# Sheet1.net
KiCad netlist of a schematic drawn in Altium Designer
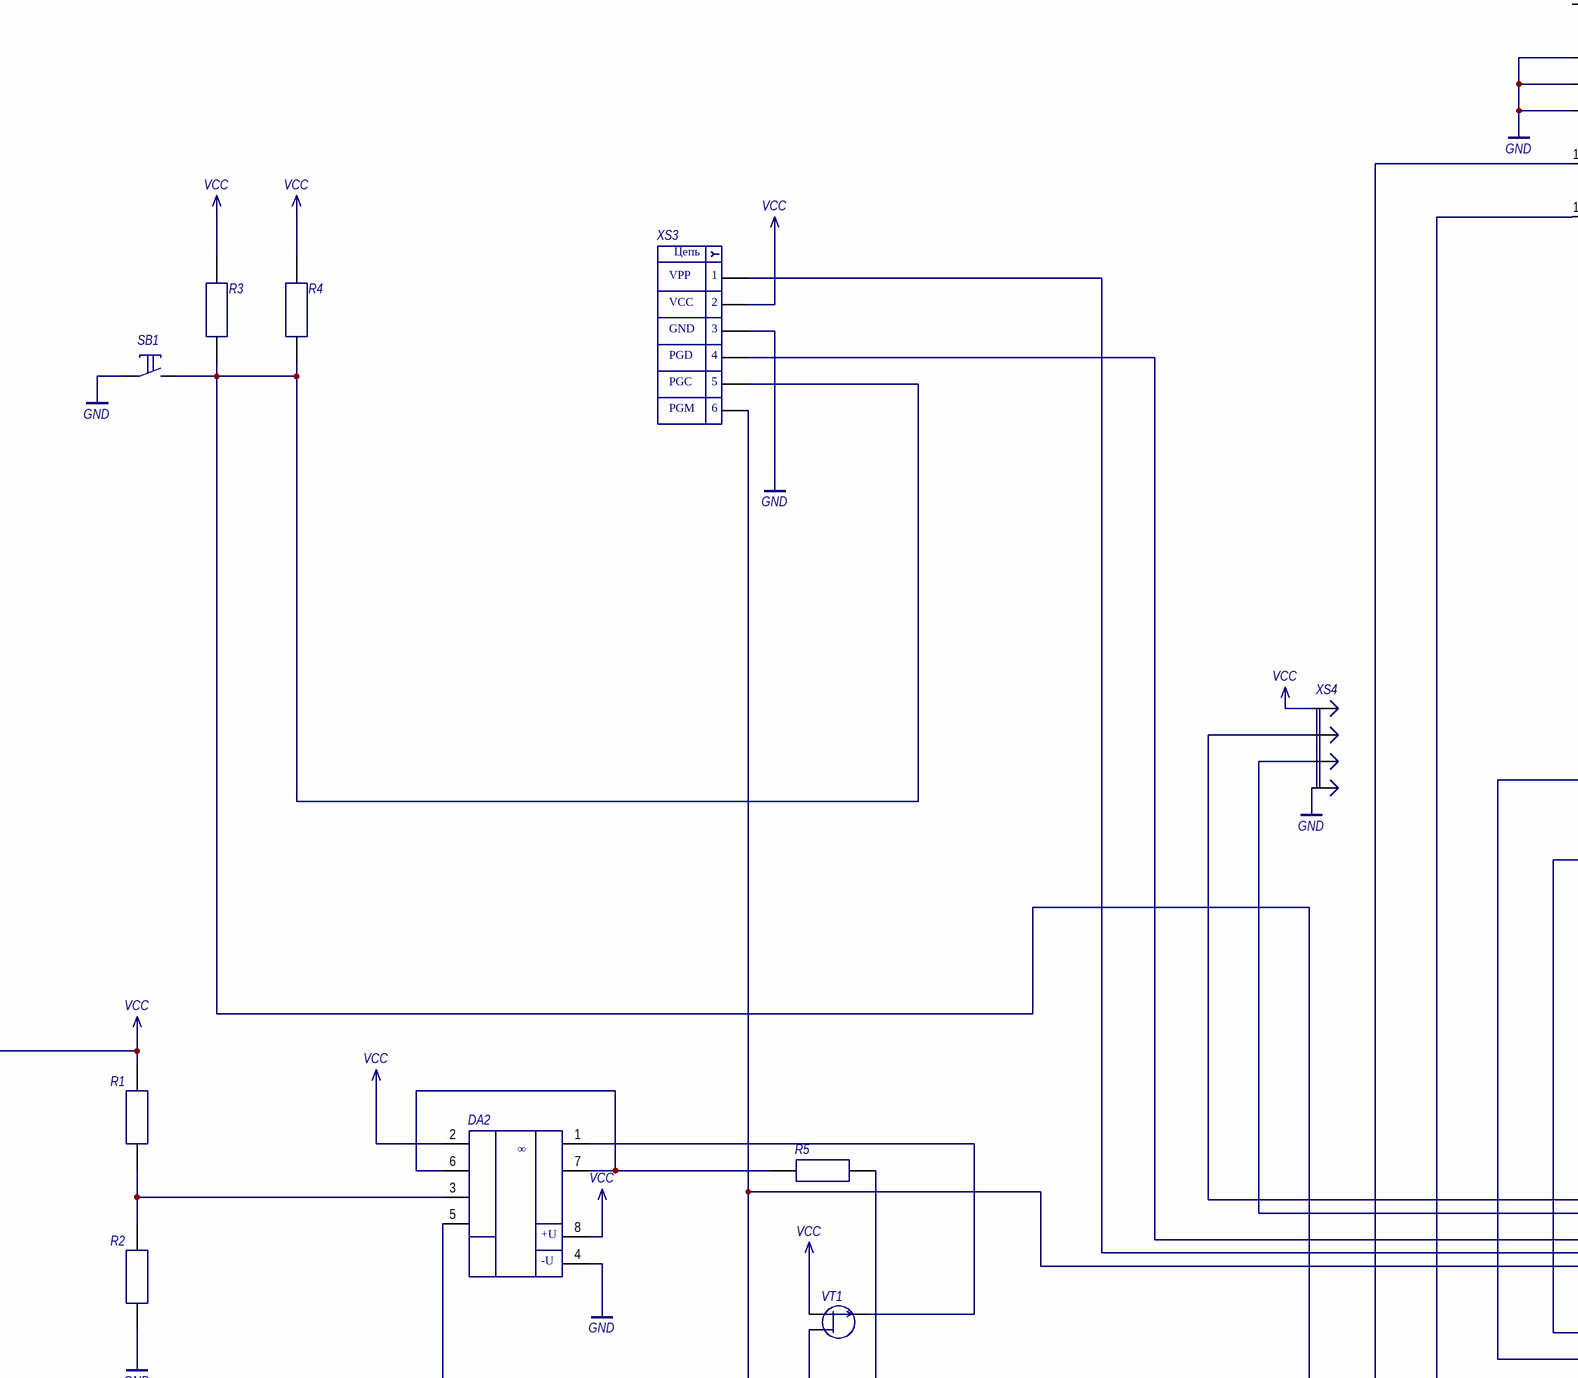
[diagram p0: Sheet1.SchDoc, top left]
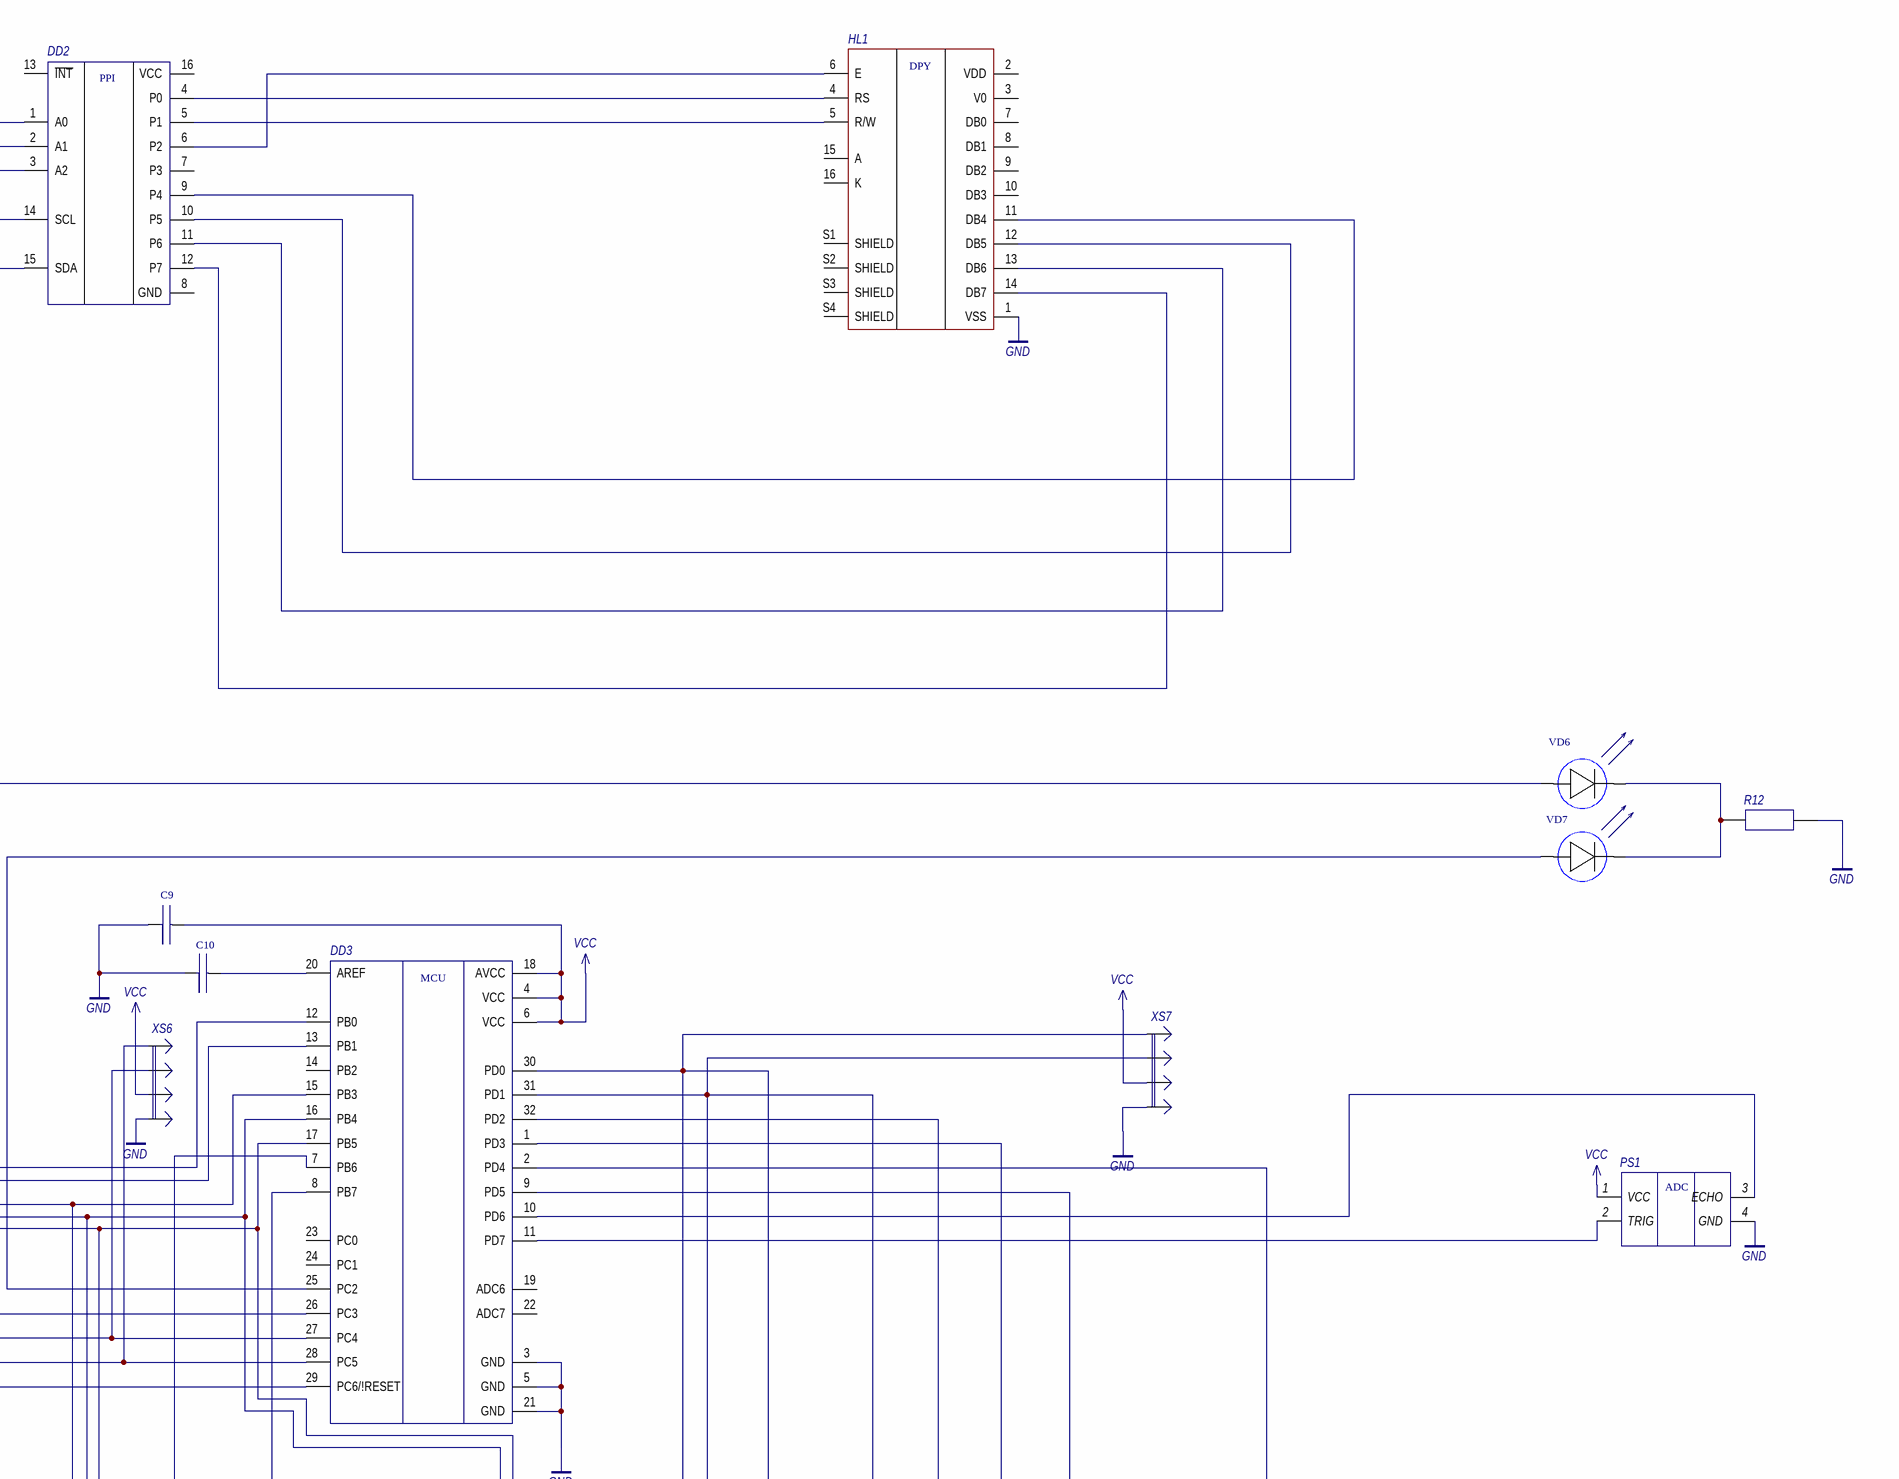
[diagram p1: Sheet1.SchDoc, top right]
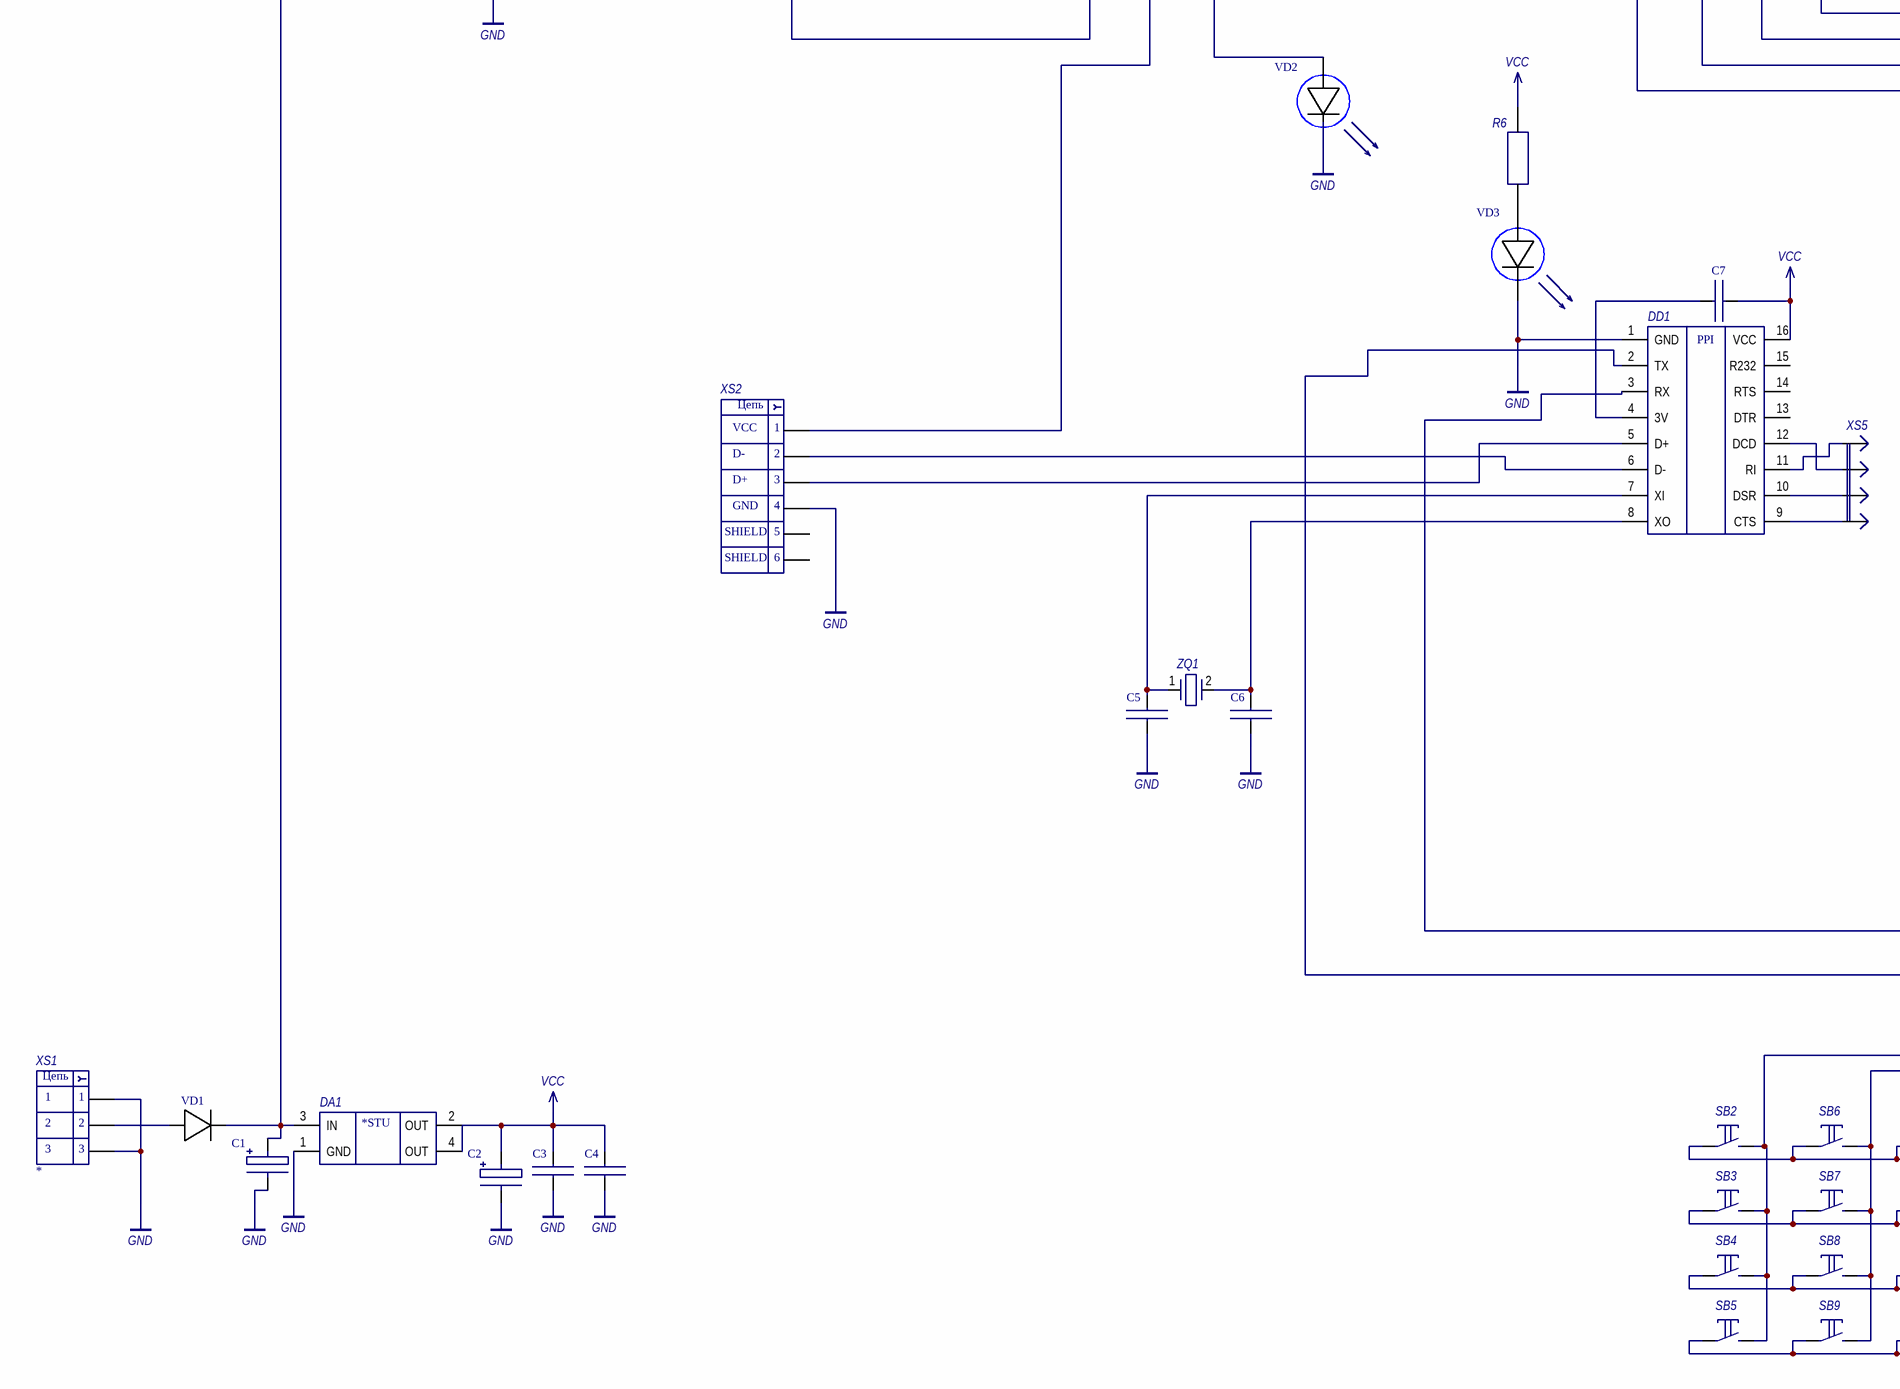
[diagram p2: Sheet1.SchDoc, bottom left]
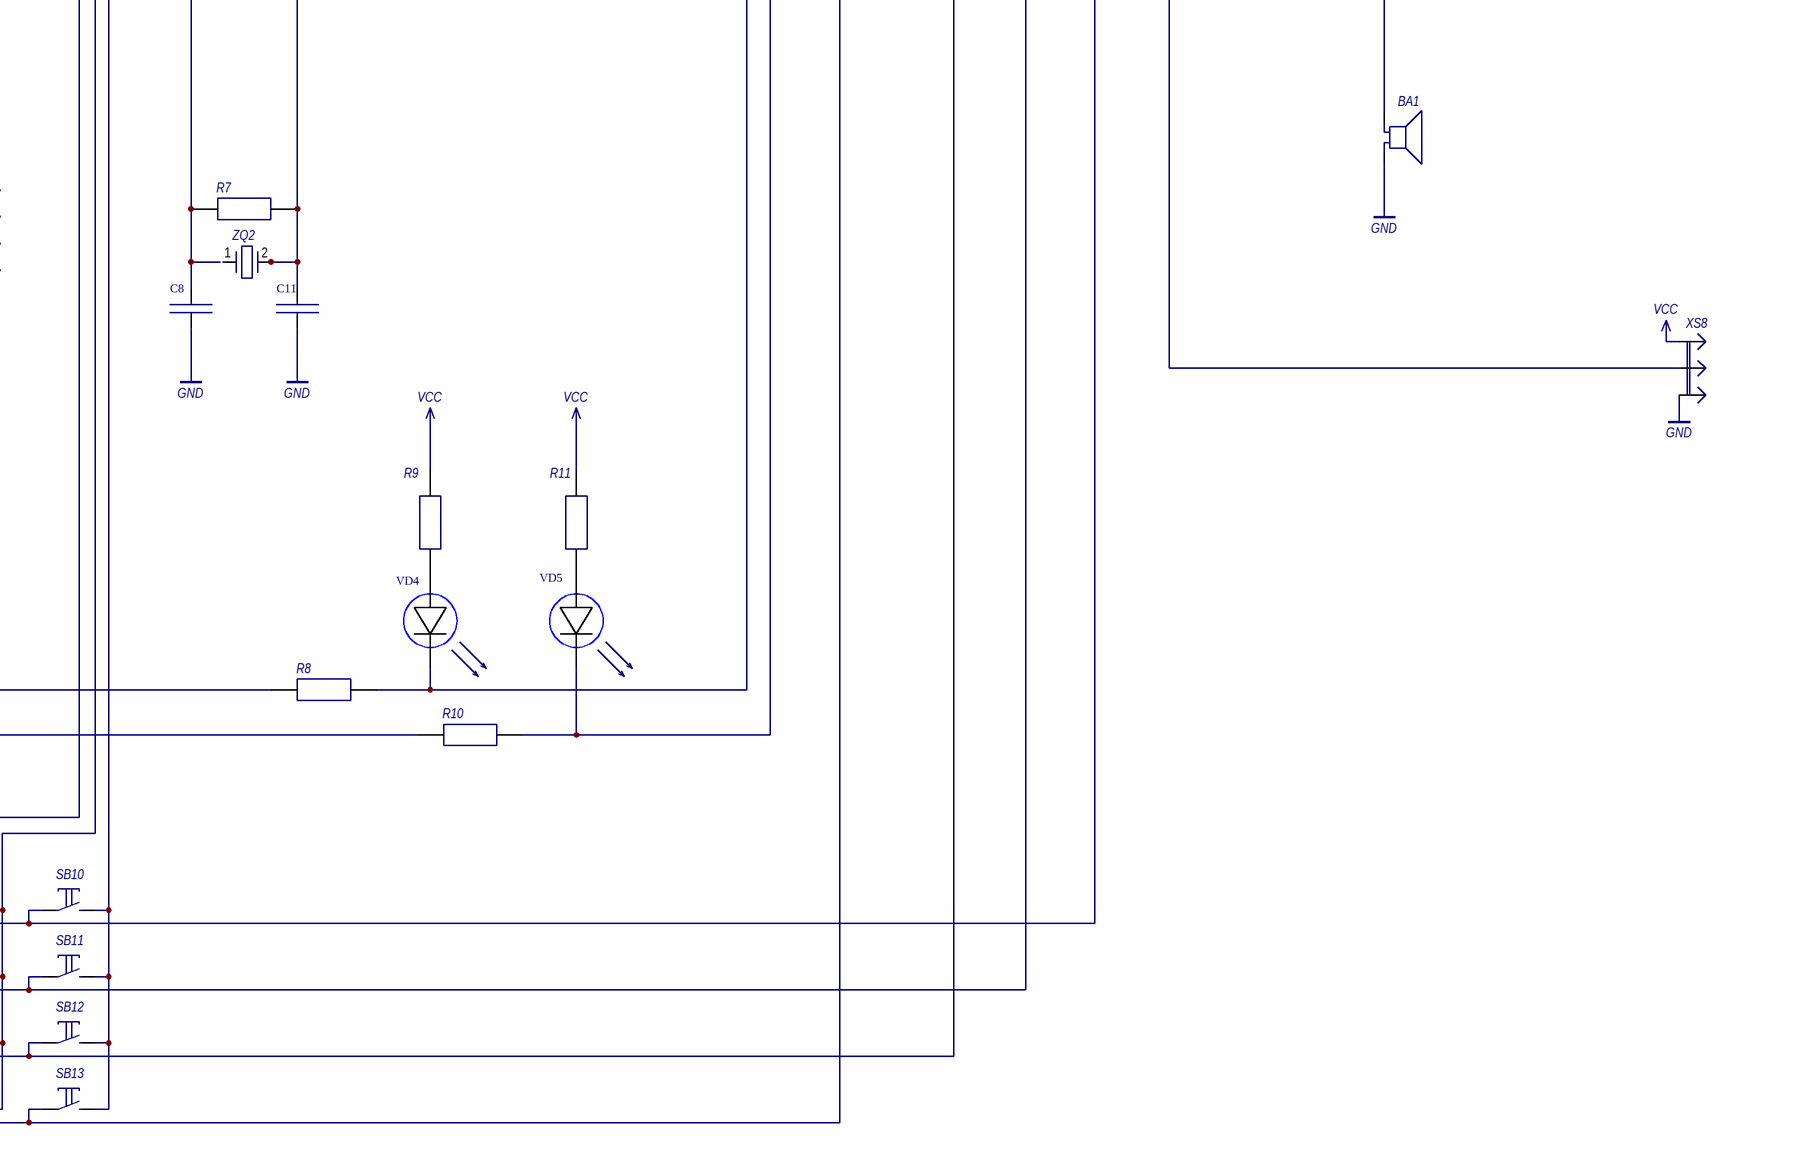
[diagram p3: Sheet1.SchDoc, bottom right]

(export (version "E")
  (design (tool "Eeschema 10.0.6"))
  (components
    (comp (ref "BA1")
      (value "*")
      (footprint "CUI_CVS-3108")
      (description "31.8 mm, Round Frame, 0.1 W, 8 Ohm, Neodymium Magnet, Mylar Cone, Speaker")
      (fields (field (name "MF") "CUI Devices") (field (name "MP") "CVS-3108"))
      (libsource (lib "CVS-3108") (part "CVS-3108"))
    )
    (comp (ref "C1")
      (value "UPM1C152MHD")
      (footprint "M7:SMA/DO-214AC_DTC")
      (description "1500ÂµF 16V Aluminum Electrolytic Capacitors Radial, Can 5000 Hrs @ 105Â°C")
      (fields (field (name "MF") "Nichicon"))
      (libsource (lib "UPM1C152MHD") (part "UPM1C152MHD"))
    )
    (comp (ref "C2")
      (value "UPM1C152MHD")
      (footprint "M7:SMA/DO-214AC_DTC")
      (description "1500ÂµF 16V Aluminum Electrolytic Capacitors Radial, Can 5000 Hrs @ 105Â°C")
      (fields (field (name "MF") "Nichicon"))
      (libsource (lib "UPM1C152MHD") (part "UPM1C152MHD"))
    )
    (comp (ref "C3")
      (value "1808Y5K00101JXT")
      (footprint "CAPC4520X200N:CAPC4520X200N")
      (libsource (lib "1808Y5K00101JXT") (part "1808Y5K00101JXT"))
    )
    (comp (ref "C4")
      (value "1808Y5K00101JXT")
      (footprint "CAPC4520X200N:CAPC4520X200N")
      (libsource (lib "1808Y5K00101JXT") (part "1808Y5K00101JXT"))
    )
    (comp (ref "C5")
      (value "1808Y5K00101JXT")
      (footprint "CAPC4520X200N:CAPC4520X200N")
      (libsource (lib "1808Y5K00101JXT") (part "1808Y5K00101JXT"))
    )
    (comp (ref "C6")
      (value "1808Y5K00101JXT")
      (footprint "CAPC4520X200N:CAPC4520X200N")
      (libsource (lib "1808Y5K00101JXT") (part "1808Y5K00101JXT"))
    )
    (comp (ref "C7")
      (value "1808Y5K00101JXT")
      (footprint "CAPC4520X200N:CAPC4520X200N")
      (libsource (lib "1808Y5K00101JXT") (part "1808Y5K00101JXT"))
    )
    (comp (ref "C8")
      (value "1808Y5K00101JXT")
      (footprint "CAPC4520X200N:CAPC4520X200N")
      (libsource (lib "1808Y5K00101JXT") (part "1808Y5K00101JXT"))
    )
    (comp (ref "C9")
      (value "1808Y5K00101JXT")
      (footprint "CAPC4520X200N:CAPC4520X200N")
      (libsource (lib "1808Y5K00101JXT") (part "1808Y5K00101JXT"))
    )
    (comp (ref "C10")
      (value "1808Y5K00101JXT")
      (footprint "CAPC4520X200N:CAPC4520X200N")
      (libsource (lib "1808Y5K00101JXT") (part "1808Y5K00101JXT"))
    )
    (comp (ref "C11")
      (value "1808Y5K00101JXT")
      (footprint "CAPC4520X200N:CAPC4520X200N")
      (libsource (lib "1808Y5K00101JXT") (part "1808Y5K00101JXT"))
    )
    (comp (ref "DA1")
      (value "*")
      (footprint "SOT230P700X180-4N")
      (description "Linear Voltage Regulator IC 1 Output 1A SOT-223")
      (fields (field (name "MP") "NCP1117ST50T3G") (field (name "MF") "ON Semiconductor"))
      (libsource (lib "NCP1117ST50T3G") (part "NCP1117ST50T3G"))
    )
    (comp (ref "DA2")
      (value "*")
      (footprint "SOIC127P599X175-8N")
      (description "Dual standard operational amplifier 8-SOIC 0 to 70")
      (fields (field (name "DIGI-KEY_PART_NUMBER") "296-1014-2-ND") (field (name "MP") "LM358D"))
      (libsource (lib "LM358D") (part "LM358D"))
    )
    (comp (ref "DD1")
      (value "*")
      (footprint "SOIC127P1030X265-16N")
      (description "Circuit Breaker Magnetic 3Pole 40A 240VAC")
      (fields (field (name "MF") "Eaton") (field (name "MP") "CH340"))
      (libsource (lib "CH340") (part "CH340"))
    )
    (comp (ref "DD2")
      (value "*")
      (footprint "DIP794W45P254L1969H508Q16")
      (description "Remote 8-Bit I/O Expander for I2C-Bus")
      (fields (field (name "MF") "Texas Instruments") (field (name "MP") "PCF8574N"))
      (libsource (lib "PCF8574N") (part "PCF8574N"))
    )
    (comp (ref "DD3")
      (value "*")
      (footprint "QFP80P900X900X120-32N")
      (description "AVR AVRÂ® ATmega Microcontroller IC 8-Bit 20MHz 32KB _16K x 16_ FLASH 32-TQFP _7x7_")
      (fields (field (name "MP") "ATMEGA328P-AU") (field (name "MF") "Microchip"))
      (libsource (lib "ATMEGA328P-AU") (part "ATMEGA328P-AU"))
    )
    (comp (ref "HL1")
      (value "*")
      (footprint "LCD_LCD-20X4B")
      (description "Display Development Tools 20X4 CHARACTER BLUE LCD W/BACKLIGHT")
      (fields (field (name "MF") "Gravitech") (field (name "MP") "LCD-20X4B"))
      (libsource (lib "LCD-20X4B") (part "LCD-20X4B"))
    )
    (comp (ref "PS1")
      (value "*")
      (footprint "XCVR_HC-SR04")
      (description "HC-SR04 Ultrasonic Sensor Platform Evaluation Expansion Board")
      (fields (field (name "MP") "HC-SR04") (field (name "MF") "SparkFun Electronics"))
      (libsource (lib "HC-SR04") (part "HC-SR04"))
    )
    (comp (ref "R1")
      (value "*")
      (footprint "CAPC4520X200N:CAPC4520X200N")
      (libsource (lib "R") (part "Component_1"))
    )
    (comp (ref "R2")
      (value "*")
      (footprint "CAPC4520X200N:CAPC4520X200N")
      (libsource (lib "R") (part "Component_1"))
    )
    (comp (ref "R3")
      (value "*")
      (footprint "CAPC4520X200N:CAPC4520X200N")
      (libsource (lib "R") (part "Component_1"))
    )
    (comp (ref "R4")
      (value "*")
      (footprint "CAPC4520X200N:CAPC4520X200N")
      (libsource (lib "R") (part "Component_1"))
    )
    (comp (ref "R5")
      (value "*")
      (footprint "CAPC4520X200N:CAPC4520X200N")
      (libsource (lib "R") (part "Component_1"))
    )
    (comp (ref "R6")
      (value "*")
      (footprint "CAPC4520X200N:CAPC4520X200N")
      (libsource (lib "R") (part "Component_1"))
    )
    (comp (ref "R7")
      (value "*")
      (footprint "CAPC4520X200N:CAPC4520X200N")
      (libsource (lib "R") (part "Component_1"))
    )
    (comp (ref "R8")
      (value "*")
      (footprint "CAPC4520X200N:CAPC4520X200N")
      (libsource (lib "R") (part "Component_1"))
    )
    (comp (ref "R9")
      (value "*")
      (footprint "CAPC4520X200N:CAPC4520X200N")
      (libsource (lib "R") (part "Component_1"))
    )
    (comp (ref "R10")
      (value "*")
      (footprint "CAPC4520X200N:CAPC4520X200N")
      (libsource (lib "R") (part "Component_1"))
    )
    (comp (ref "R11")
      (value "*")
      (footprint "CAPC4520X200N:CAPC4520X200N")
      (libsource (lib "R") (part "Component_1"))
    )
    (comp (ref "R12")
      (value "*")
      (footprint "CAPC4520X200N:CAPC4520X200N")
      (libsource (lib "R") (part "Component_1"))
    )
    (comp (ref "SB1")
      (value "4-1437565-9")
      (footprint "TE_4-1437565-9")
      (description "Switch Tactile OFF _ON_ SPST Round Button Gull Wing 0.05A 12VDC 1.57N SMD Loose Piece")
      (fields (field (name "MF") "TE Connectivity") (field (name "DIGI-KEY_PART_NUMBER") "450-1133-ND"))
      (libsource (lib "4-1437565-9") (part "4-1437565-9"))
    )
    (comp (ref "SB2")
      (value "4-1437565-9")
      (footprint "TE_4-1437565-9")
      (description "Switch Tactile OFF _ON_ SPST Round Button Gull Wing 0.05A 12VDC 1.57N SMD Loose Piece")
      (fields (field (name "MF") "TE Connectivity") (field (name "DIGI-KEY_PART_NUMBER") "450-1133-ND"))
      (libsource (lib "4-1437565-9") (part "4-1437565-9"))
    )
    (comp (ref "SB3")
      (value "4-1437565-9")
      (footprint "TE_4-1437565-9")
      (description "Switch Tactile OFF _ON_ SPST Round Button Gull Wing 0.05A 12VDC 1.57N SMD Loose Piece")
      (fields (field (name "MF") "TE Connectivity") (field (name "DIGI-KEY_PART_NUMBER") "450-1133-ND"))
      (libsource (lib "4-1437565-9") (part "4-1437565-9"))
    )
    (comp (ref "SB4")
      (value "4-1437565-9")
      (footprint "TE_4-1437565-9")
      (description "Switch Tactile OFF _ON_ SPST Round Button Gull Wing 0.05A 12VDC 1.57N SMD Loose Piece")
      (fields (field (name "MF") "TE Connectivity") (field (name "DIGI-KEY_PART_NUMBER") "450-1133-ND"))
      (libsource (lib "4-1437565-9") (part "4-1437565-9"))
    )
    (comp (ref "SB5")
      (value "4-1437565-9")
      (footprint "TE_4-1437565-9")
      (description "Switch Tactile OFF _ON_ SPST Round Button Gull Wing 0.05A 12VDC 1.57N SMD Loose Piece")
      (fields (field (name "MF") "TE Connectivity") (field (name "DIGI-KEY_PART_NUMBER") "450-1133-ND"))
      (libsource (lib "4-1437565-9") (part "4-1437565-9"))
    )
    (comp (ref "SB6")
      (value "4-1437565-9")
      (footprint "TE_4-1437565-9")
      (description "Switch Tactile OFF _ON_ SPST Round Button Gull Wing 0.05A 12VDC 1.57N SMD Loose Piece")
      (fields (field (name "MF") "TE Connectivity") (field (name "DIGI-KEY_PART_NUMBER") "450-1133-ND"))
      (libsource (lib "4-1437565-9") (part "4-1437565-9"))
    )
    (comp (ref "SB7")
      (value "4-1437565-9")
      (footprint "TE_4-1437565-9")
      (description "Switch Tactile OFF _ON_ SPST Round Button Gull Wing 0.05A 12VDC 1.57N SMD Loose Piece")
      (fields (field (name "MF") "TE Connectivity") (field (name "DIGI-KEY_PART_NUMBER") "450-1133-ND"))
      (libsource (lib "4-1437565-9") (part "4-1437565-9"))
    )
    (comp (ref "SB8")
      (value "4-1437565-9")
      (footprint "TE_4-1437565-9")
      (description "Switch Tactile OFF _ON_ SPST Round Button Gull Wing 0.05A 12VDC 1.57N SMD Loose Piece")
      (fields (field (name "MF") "TE Connectivity") (field (name "DIGI-KEY_PART_NUMBER") "450-1133-ND"))
      (libsource (lib "4-1437565-9") (part "4-1437565-9"))
    )
    (comp (ref "SB9")
      (value "4-1437565-9")
      (footprint "TE_4-1437565-9")
      (description "Switch Tactile OFF _ON_ SPST Round Button Gull Wing 0.05A 12VDC 1.57N SMD Loose Piece")
      (fields (field (name "MF") "TE Connectivity") (field (name "DIGI-KEY_PART_NUMBER") "450-1133-ND"))
      (libsource (lib "4-1437565-9") (part "4-1437565-9"))
    )
    (comp (ref "SB10")
      (value "4-1437565-9")
      (footprint "TE_4-1437565-9")
      (description "Switch Tactile OFF _ON_ SPST Round Button Gull Wing 0.05A 12VDC 1.57N SMD Loose Piece")
      (fields (field (name "MF") "TE Connectivity") (field (name "DIGI-KEY_PART_NUMBER") "450-1133-ND"))
      (libsource (lib "4-1437565-9") (part "4-1437565-9"))
    )
    (comp (ref "SB11")
      (value "4-1437565-9")
      (footprint "TE_4-1437565-9")
      (description "Switch Tactile OFF _ON_ SPST Round Button Gull Wing 0.05A 12VDC 1.57N SMD Loose Piece")
      (fields (field (name "MF") "TE Connectivity") (field (name "DIGI-KEY_PART_NUMBER") "450-1133-ND"))
      (libsource (lib "4-1437565-9") (part "4-1437565-9"))
    )
    (comp (ref "SB12")
      (value "4-1437565-9")
      (footprint "TE_4-1437565-9")
      (description "Switch Tactile OFF _ON_ SPST Round Button Gull Wing 0.05A 12VDC 1.57N SMD Loose Piece")
      (fields (field (name "MF") "TE Connectivity") (field (name "DIGI-KEY_PART_NUMBER") "450-1133-ND"))
      (libsource (lib "4-1437565-9") (part "4-1437565-9"))
    )
    (comp (ref "SB13")
      (value "4-1437565-9")
      (footprint "TE_4-1437565-9")
      (description "Switch Tactile OFF _ON_ SPST Round Button Gull Wing 0.05A 12VDC 1.57N SMD Loose Piece")
      (fields (field (name "MF") "TE Connectivity") (field (name "DIGI-KEY_PART_NUMBER") "450-1133-ND"))
      (libsource (lib "4-1437565-9") (part "4-1437565-9"))
    )
    (comp (ref "VD1")
      (value "1N4007")
      (footprint "SnapEDApcb:DIOAD1060W80L520D270")
      (description "Diode Standard 1000V 1A Through Hole DO-204AL _DO-41_")
      (fields (field (name "MF") "ON Semiconductor"))
      (libsource (lib "SnapEDAsch") (part "1N4007"))
    )
    (comp (ref "VD2")
      (value "CLA1A-WKW-CXAYB153")
      (footprint "SnapEDApcb:SOJ150P350X210-4N")
      (description "LED Lighting - White, Cool 5500K 3.6V 30mA 4-PLCC")
      (fields (field (name "MF") "Cree Inc.") (field (name "DIGI-KEY_PART_NUMBER") "CLA1A-WKW-CXAYB153CT-ND"))
      (libsource (lib "SnapEDAsch") (part "CLA1A-WKW-CXAYB153"))
    )
    (comp (ref "VD3")
      (value "CLA1A-WKW-CXAYB153")
      (footprint "SnapEDApcb:SOJ150P350X210-4N")
      (description "LED Lighting - White, Cool 5500K 3.6V 30mA 4-PLCC")
      (fields (field (name "MF") "Cree Inc.") (field (name "DIGI-KEY_PART_NUMBER") "CLA1A-WKW-CXAYB153CT-ND"))
      (libsource (lib "SnapEDAsch") (part "CLA1A-WKW-CXAYB153"))
    )
    (comp (ref "VD4")
      (value "CLA1A-WKW-CXAYB153")
      (footprint "SnapEDApcb:SOJ150P350X210-4N")
      (description "LED Lighting - White, Cool 5500K 3.6V 30mA 4-PLCC")
      (fields (field (name "MF") "Cree Inc.") (field (name "DIGI-KEY_PART_NUMBER") "CLA1A-WKW-CXAYB153CT-ND"))
      (libsource (lib "SnapEDAsch") (part "CLA1A-WKW-CXAYB153"))
    )
    (comp (ref "VD5")
      (value "CLA1A-WKW-CXAYB153")
      (footprint "SnapEDApcb:SOJ150P350X210-4N")
      (description "LED Lighting - White, Cool 5500K 3.6V 30mA 4-PLCC")
      (fields (field (name "MF") "Cree Inc.") (field (name "DIGI-KEY_PART_NUMBER") "CLA1A-WKW-CXAYB153CT-ND"))
      (libsource (lib "SnapEDAsch") (part "CLA1A-WKW-CXAYB153"))
    )
    (comp (ref "VD6")
      (value "CLA1A-WKW-CXAYB153")
      (footprint "SnapEDApcb:SOJ150P350X210-4N")
      (description "LED Lighting - White, Cool 5500K 3.6V 30mA 4-PLCC")
      (fields (field (name "MF") "Cree Inc.") (field (name "DIGI-KEY_PART_NUMBER") "CLA1A-WKW-CXAYB153CT-ND"))
      (libsource (lib "SnapEDAsch") (part "CLA1A-WKW-CXAYB153"))
    )
    (comp (ref "VD7")
      (value "CLA1A-WKW-CXAYB153")
      (footprint "SnapEDApcb:SOJ150P350X210-4N")
      (description "LED Lighting - White, Cool 5500K 3.6V 30mA 4-PLCC")
      (fields (field (name "MF") "Cree Inc.") (field (name "DIGI-KEY_PART_NUMBER") "CLA1A-WKW-CXAYB153CT-ND"))
      (libsource (lib "SnapEDAsch") (part "CLA1A-WKW-CXAYB153"))
    )
    (comp (ref "VT1")
      (value "*")
      (footprint "SOT95P237X112-3N")
      (fields (field (name "MF") "Infineon") (field (name "MP") "IRLML6402TRPBF"))
      (libsource (lib "IRLML6402TRPBF") (part "IRLML6402TRPBF"))
    )
    (comp (ref "XS1")
      (value "*")
      (footprint "CUI_PJ-038B")
      (description "2.5 x 6.2 mm, 2.5 A, Horizontal, Panel Mount, Dc Power Jack Connector")
      (fields (field (name "MF") "CUI Devices") (field (name "MP") "PJ-038B"))
      (libsource (lib "PJ-038B") (part "PJ-038B"))
    )
    (comp (ref "XS2")
      (value "*")
      (footprint "SAMTEC_USB-B-S-X-X-TH")
      (description "USB-B (USB TYPE-B) USB 2.0 Receptacle Connector 4 Position Through Hole, Right Angle")
      (fields (field (name "MP") "USB-B-S-S-B-TH") (field (name "MF") "Samtec"))
      (libsource (lib "USB-B-S-X-X-TH") (part "USB-B-S-X-X-TH"))
    )
    (comp (ref "XS3")
      (value "*")
      (footprint "MOLEX-1X6")
      (description "MICROCHIP ICSP PROG ADAPTER SET")
      (fields (field (name "MP") "PIC-ICSP") (field (name "MF") "Olimex LTD"))
      (libsource (lib "PIC-ICSP") (part "PIC-ICSP"))
    )
    (comp (ref "XS4")
      (value "*")
      (footprint "SAMTEC_TW-02-03-T-D-335-100")
      (description "4 Position Header Spacer Connector 0.079 (2.00mm) Tin Through Hole")
      (fields (field (name "MP") "TW-02-03-T-D-335-100") (field (name "MF") "Samtec"))
      (libsource (lib "TW-02-03-T-D-335-100") (part "TW-02-03-T-D-335-100"))
    )
    (comp (ref "XS5")
      (value "*")
      (footprint "SAMTEC_TW-02-03-T-D-335-100")
      (description "4 Position Header Spacer Connector 0.079 (2.00mm) Tin Through Hole")
      (fields (field (name "MP") "TW-02-03-T-D-335-100") (field (name "MF") "Samtec"))
      (libsource (lib "TW-02-03-T-D-335-100") (part "TW-02-03-T-D-335-100"))
    )
    (comp (ref "XS6")
      (value "*")
      (footprint "SAMTEC_TW-02-03-T-D-335-100")
      (description "4 Position Header Spacer Connector 0.079 (2.00mm) Tin Through Hole")
      (fields (field (name "MP") "TW-02-03-T-D-335-100") (field (name "MF") "Samtec"))
      (libsource (lib "TW-02-03-T-D-335-100") (part "TW-02-03-T-D-335-100"))
    )
    (comp (ref "XS7")
      (value "*")
      (footprint "SAMTEC_TW-02-03-T-D-335-100")
      (description "4 Position Header Spacer Connector 0.079 (2.00mm) Tin Through Hole")
      (fields (field (name "MP") "TW-02-03-T-D-335-100") (field (name "MF") "Samtec"))
      (libsource (lib "TW-02-03-T-D-335-100") (part "TW-02-03-T-D-335-100"))
    )
    (comp (ref "XS8")
      (value "*")
      (footprint "SAMTEC_TW-03-12-L-S-765-200")
      (description "CONN BRD STACK 2.00 3POS")
      (fields (field (name "MP") "TW-03-12-L-S-765-200") (field (name "MF") "Samtec"))
      (libsource (lib "TW-03-12-L-S-765-200") (part "TW-03-12-L-S-765-200"))
    )
    (comp (ref "ZQ1")
      (value "*")
      (footprint "XTAL500X320X130N")
      (description "16MHz Â±30ppm Crystal 18pF 40 Ohms 2-SMD, No Lead")
      (fields
        (field (name "DIGI-KEY_PART_NUMBER") "535-13579-1-ND")
        (field (name "MP") "ABM3-16.000MHZ-B4Y-T")
      )
      (libsource (lib "ABM3-16.000MHZ-B4Y-T") (part "ABM3-16.000MHZ-B4Y-T"))
    )
    (comp (ref "ZQ2")
      (value "*")
      (footprint "XTAL500X320X130N")
      (description "16MHz Â±30ppm Crystal 18pF 40 Ohms 2-SMD, No Lead")
      (fields
        (field (name "DIGI-KEY_PART_NUMBER") "535-13579-1-ND")
        (field (name "MP") "ABM3-16.000MHZ-B4Y-T")
      )
      (libsource (lib "ABM3-16.000MHZ-B4Y-T") (part "ABM3-16.000MHZ-B4Y-T"))
    )
  )
  (nets
    (net (code "1") (name "GND") (class "Default")
      (node (ref "BA1") (pin "N") (pinfunction "N_N") (pintype "passive"))
      (node (ref "C1") (pin "N") (pinfunction "N_N") (pintype "passive"))
      (node (ref "C10") (pin "1") (pinfunction "1_1") (pintype "passive"))
      (node (ref "C11") (pin "1") (pinfunction "1_1") (pintype "passive"))
      (node (ref "C2") (pin "N") (pinfunction "N_N") (pintype "passive"))
      (node (ref "C3") (pin "1") (pinfunction "1_1") (pintype "passive"))
      (node (ref "C4") (pin "1") (pinfunction "1_1") (pintype "passive"))
      (node (ref "C5") (pin "1") (pinfunction "1_1") (pintype "passive"))
      (node (ref "C6") (pin "1") (pinfunction "1_1") (pintype "passive"))
      (node (ref "C8") (pin "1") (pinfunction "1_1") (pintype "passive"))
      (node (ref "C9") (pin "1") (pinfunction "1_1") (pintype "passive"))
      (node (ref "DA1") (pin "1") (pinfunction "GND_1") (pintype "passive"))
      (node (ref "DA2") (pin "4") (pinfunction "V-_4") (pintype "passive"))
      (node (ref "DD1") (pin "1") (pinfunction "GND_1") (pintype "passive"))
      (node (ref "DD2") (pin "1") (pinfunction "A0_1") (pintype "passive"))
      (node (ref "DD2") (pin "2") (pinfunction "A1_2") (pintype "passive"))
      (node (ref "DD2") (pin "3") (pinfunction "A2_3") (pintype "passive"))
      (node (ref "DD3") (pin "21") (pinfunction "GND_21") (pintype "passive"))
      (node (ref "DD3") (pin "3") (pinfunction "GND_3") (pintype "passive"))
      (node (ref "DD3") (pin "5") (pinfunction "GND_5") (pintype "passive"))
      (node (ref "HL1") (pin "1") (pinfunction "VSS_1") (pintype "passive"))
      (node (ref "PS1") (pin "4") (pinfunction "GND_4") (pintype "passive"))
      (node (ref "R12") (pin "2") (pinfunction "2_2") (pintype "passive"))
      (node (ref "R2") (pin "1") (pinfunction "1_1") (pintype "passive"))
      (node (ref "SB1") (pin "1") (pinfunction "1_1") (pintype "passive"))
      (node (ref "VD2") (pin "4") (pinfunction "C_4") (pintype "passive"))
      (node (ref "VD3") (pin "4") (pinfunction "C_4") (pintype "passive"))
      (node (ref "XS1") (pin "1") (pinfunction "1_1") (pintype "passive"))
      (node (ref "XS1") (pin "3") (pinfunction "3_3") (pintype "passive"))
      (node (ref "XS2") (pin "4") (pinfunction "GND_4") (pintype "passive"))
      (node (ref "XS3") (pin "4") (pinfunction "GND_4") (pintype "passive"))
      (node (ref "XS4") (pin "04") (pinfunction "4_04") (pintype "passive"))
      (node (ref "XS6") (pin "04") (pinfunction "4_04") (pintype "passive"))
      (node (ref "XS7") (pin "04") (pinfunction "4_04") (pintype "passive"))
      (node (ref "XS8") (pin "03") (pinfunction "03_03") (pintype "passive"))
    )
    (net (code "2") (name "Net-(DA2-IN1+)") (class "Default")
      (node (ref "DA2") (pin "3") (pinfunction "IN1+_3") (pintype "passive"))
      (node (ref "R1") (pin "1") (pinfunction "1_1") (pintype "passive"))
      (node (ref "R2") (pin "2") (pinfunction "2_2") (pintype "passive"))
    )
    (net (code "3") (name "Net-(DA2-IN2+)") (class "Default")
      (node (ref "DA2") (pin "5") (pinfunction "IN2+_5") (pintype "passive"))
      (node (ref "DD3") (pin "17") (pinfunction "PB5_17") (pintype "passive"))
      (node (ref "DD3") (pin "30") (pinfunction "PD0_30") (pintype "passive"))
      (node (ref "R8") (pin "2") (pinfunction "2_2") (pintype "passive"))
      (node (ref "SB10") (pin "3") (pinfunction "3_3") (pintype "passive"))
      (node (ref "SB11") (pin "3") (pinfunction "3_3") (pintype "passive"))
      (node (ref "SB12") (pin "3") (pinfunction "3_3") (pintype "passive"))
      (node (ref "SB13") (pin "1") (pinfunction "1_1") (pintype "passive"))
      (node (ref "SB13") (pin "3") (pinfunction "3_3") (pintype "passive"))
      (node (ref "SB5") (pin "1") (pinfunction "1_1") (pintype "passive"))
      (node (ref "SB9") (pin "1") (pinfunction "1_1") (pintype "passive"))
      (node (ref "VD4") (pin "4") (pinfunction "C_4") (pintype "passive"))
      (node (ref "XS3") (pin "1") (pinfunction "PGM_1") (pintype "passive"))
      (node (ref "XS7") (pin "01") (pinfunction "01_01") (pintype "passive"))
    )
    (net (code "4") (name "Net-(DA2-IN2-)") (class "Default")
      (node (ref "DA2") (pin "6") (pinfunction "IN2-_6") (pintype "passive"))
      (node (ref "DA2") (pin "7") (pinfunction "OUT2_7") (pintype "passive"))
      (node (ref "R5") (pin "1") (pinfunction "1_1") (pintype "passive"))
    )
    (net (code "5") (name "Net-(DA2-OUT1)") (class "Default")
      (node (ref "DA2") (pin "1") (pinfunction "OUT1_1") (pintype "passive"))
      (node (ref "VT1") (pin "1") (pinfunction "G_1") (pintype "passive"))
    )
    (net (code "6") (name "Net-(DD1-3V)") (class "Default")
      (node (ref "C7") (pin "2") (pinfunction "2_2") (pintype "passive"))
      (node (ref "DD1") (pin "4") (pinfunction "3V_4") (pintype "passive"))
    )
    (net (code "7") (name "Net-(DD1-CTS)") (class "Default")
      (node (ref "DD1") (pin "9") (pinfunction "CTS_9") (pintype "passive"))
      (node (ref "XS5") (pin "04") (pinfunction "4_04") (pintype "passive"))
    )
    (net (code "8") (name "Net-(DD1-D+)") (class "Default")
      (node (ref "DD1") (pin "5") (pinfunction "D+_5") (pintype "passive"))
      (node (ref "XS2") (pin "3") (pinfunction "D+_3") (pintype "passive"))
    )
    (net (code "9") (name "Net-(DD1-D-)") (class "Default")
      (node (ref "DD1") (pin "6") (pinfunction "D-_6") (pintype "passive"))
      (node (ref "XS2") (pin "2") (pinfunction "D-_2") (pintype "passive"))
    )
    (net (code "10") (name "Net-(DD1-DCD)") (class "Default")
      (node (ref "DD1") (pin "12") (pinfunction "DCD_12") (pintype "passive"))
      (node (ref "XS5") (pin "02") (pinfunction "02_02") (pintype "passive"))
    )
    (net (code "11") (name "Net-(DD1-DSR)") (class "Default")
      (node (ref "DD1") (pin "10") (pinfunction "DSR_10") (pintype "passive"))
      (node (ref "XS5") (pin "03") (pinfunction "03_03") (pintype "passive"))
    )
    (net (code "12") (name "Net-(DD1-RI)") (class "Default")
      (node (ref "DD1") (pin "11") (pinfunction "RI_11") (pintype "passive"))
      (node (ref "XS5") (pin "01") (pinfunction "01_01") (pintype "passive"))
    )
    (net (code "13") (name "Net-(DD1-RX)") (class "Default")
      (node (ref "DD1") (pin "3") (pinfunction "RX_3") (pintype "passive"))
      (node (ref "R8") (pin "1") (pinfunction "1_1") (pintype "passive"))
    )
    (net (code "14") (name "Net-(DD1-TX)") (class "Default")
      (node (ref "DD1") (pin "2") (pinfunction "TX_2") (pintype "passive"))
      (node (ref "R10") (pin "1") (pinfunction "1_1") (pintype "passive"))
    )
    (net (code "15") (name "Net-(DD1-XI)") (class "Default")
      (node (ref "C5") (pin "2") (pinfunction "2_2") (pintype "passive"))
      (node (ref "DD1") (pin "7") (pinfunction "XI_7") (pintype "passive"))
      (node (ref "ZQ1") (pin "1") (pinfunction "1_1") (pintype "passive"))
    )
    (net (code "16") (name "Net-(DD1-XO)") (class "Default")
      (node (ref "C6") (pin "2") (pinfunction "2_2") (pintype "passive"))
      (node (ref "DD1") (pin "8") (pinfunction "XO_8") (pintype "passive"))
      (node (ref "ZQ1") (pin "2") (pinfunction "2_2") (pintype "passive"))
    )
    (net (code "17") (name "Net-(DD2-P0)") (class "Default")
      (node (ref "DD2") (pin "4") (pinfunction "P0_4") (pintype "passive"))
      (node (ref "HL1") (pin "4") (pinfunction "RS_4") (pintype "passive"))
    )
    (net (code "18") (name "Net-(DD2-P1)") (class "Default")
      (node (ref "DD2") (pin "5") (pinfunction "P1_5") (pintype "passive"))
      (node (ref "HL1") (pin "5") (pinfunction "R/W_5") (pintype "passive"))
    )
    (net (code "19") (name "Net-(DD2-P2)") (class "Default")
      (node (ref "DD2") (pin "6") (pinfunction "P2_6") (pintype "passive"))
      (node (ref "HL1") (pin "6") (pinfunction "E_6") (pintype "passive"))
    )
    (net (code "20") (name "Net-(DD2-P4)") (class "Default")
      (node (ref "DD2") (pin "9") (pinfunction "P4_9") (pintype "passive"))
      (node (ref "HL1") (pin "11") (pinfunction "DB4_11") (pintype "passive"))
    )
    (net (code "21") (name "Net-(DD2-P5)") (class "Default")
      (node (ref "DD2") (pin "10") (pinfunction "P5_10") (pintype "passive"))
      (node (ref "HL1") (pin "12") (pinfunction "DB5_12") (pintype "passive"))
    )
    (net (code "22") (name "Net-(DD2-P6)") (class "Default")
      (node (ref "DD2") (pin "11") (pinfunction "P6_11") (pintype "passive"))
      (node (ref "HL1") (pin "13") (pinfunction "DB6_13") (pintype "passive"))
    )
    (net (code "23") (name "Net-(DD2-P7)") (class "Default")
      (node (ref "DD2") (pin "12") (pinfunction "P7_12") (pintype "passive"))
      (node (ref "HL1") (pin "14") (pinfunction "DB7_14") (pintype "passive"))
    )
    (net (code "24") (name "Net-(DD2-SCL)") (class "Default")
      (node (ref "DD2") (pin "14") (pinfunction "SCL_14") (pintype "passive"))
      (node (ref "DD3") (pin "28") (pinfunction "PC5_28") (pintype "passive"))
      (node (ref "XS6") (pin "01") (pinfunction "01_01") (pintype "passive"))
    )
    (net (code "25") (name "Net-(DD2-SDA)") (class "Default")
      (node (ref "DD2") (pin "15") (pinfunction "SDA_15") (pintype "passive"))
      (node (ref "DD3") (pin "27") (pinfunction "PC4_27") (pintype "passive"))
      (node (ref "XS6") (pin "02") (pinfunction "02_02") (pintype "passive"))
    )
    (net (code "26") (name "Net-(DD3-AREF)") (class "Default")
      (node (ref "C10") (pin "2") (pinfunction "2_2") (pintype "passive"))
      (node (ref "DD3") (pin "20") (pinfunction "AREF_20") (pintype "passive"))
    )
    (net (code "27") (name "Net-(DD3-PB0)") (class "Default")
      (node (ref "DD3") (pin "12") (pinfunction "PB0_12") (pintype "passive"))
      (node (ref "XS4") (pin "02") (pinfunction "02_02") (pintype "passive"))
    )
    (net (code "28") (name "Net-(DD3-PB1)") (class "Default")
      (node (ref "DD3") (pin "13") (pinfunction "PB1_13") (pintype "passive"))
      (node (ref "XS4") (pin "03") (pinfunction "03_03") (pintype "passive"))
    )
    (net (code "29") (name "Net-(DD3-PB3)") (class "Default")
      (node (ref "DD3") (pin "15") (pinfunction "PB3_15") (pintype "passive"))
      (node (ref "SB2") (pin "3") (pinfunction "3_3") (pintype "passive"))
      (node (ref "SB3") (pin "3") (pinfunction "3_3") (pintype "passive"))
      (node (ref "SB4") (pin "3") (pinfunction "3_3") (pintype "passive"))
      (node (ref "SB5") (pin "3") (pinfunction "3_3") (pintype "passive"))
      (node (ref "XS3") (pin "3") (pinfunction "PGD_3") (pintype "passive"))
    )
    (net (code "30") (name "Net-(DD3-PB4)") (class "Default")
      (node (ref "DD3") (pin "16") (pinfunction "PB4_16") (pintype "passive"))
      (node (ref "DD3") (pin "31") (pinfunction "PD1_31") (pintype "passive"))
      (node (ref "R10") (pin "2") (pinfunction "2_2") (pintype "passive"))
      (node (ref "SB12") (pin "1") (pinfunction "1_1") (pintype "passive"))
      (node (ref "SB4") (pin "1") (pinfunction "1_1") (pintype "passive"))
      (node (ref "SB6") (pin "3") (pinfunction "3_3") (pintype "passive"))
      (node (ref "SB7") (pin "3") (pinfunction "3_3") (pintype "passive"))
      (node (ref "SB8") (pin "1") (pinfunction "1_1") (pintype "passive"))
      (node (ref "SB8") (pin "3") (pinfunction "3_3") (pintype "passive"))
      (node (ref "SB9") (pin "3") (pinfunction "3_3") (pintype "passive"))
      (node (ref "VD5") (pin "4") (pinfunction "C_4") (pintype "passive"))
      (node (ref "XS3") (pin "6") (pinfunction "VPP_6") (pintype "passive"))
      (node (ref "XS7") (pin "02") (pinfunction "02_02") (pintype "passive"))
    )
    (net (code "31") (name "Net-(DD3-PB6)") (class "Default")
      (node (ref "C8") (pin "2") (pinfunction "2_2") (pintype "passive"))
      (node (ref "DD3") (pin "7") (pinfunction "PB6_7") (pintype "passive"))
      (node (ref "R7") (pin "2") (pinfunction "2_2") (pintype "passive"))
    )
    (net (code "32") (name "Net-(DD3-PB7)") (class "Default")
      (node (ref "C11") (pin "2") (pinfunction "2_2") (pintype "passive"))
      (node (ref "DD3") (pin "8") (pinfunction "PB7_8") (pintype "passive"))
      (node (ref "R7") (pin "1") (pinfunction "1_1") (pintype "passive"))
      (node (ref "ZQ2") (pin "2") (pinfunction "2_2") (pintype "passive"))
    )
    (net (code "33") (name "Net-(DD3-PC2)") (class "Default")
      (node (ref "DD3") (pin "25") (pinfunction "PC2_25") (pintype "passive"))
      (node (ref "VD7") (pin "2") (pinfunction "A_2") (pintype "passive"))
    )
    (net (code "34") (name "Net-(DD3-PC3)") (class "Default")
      (node (ref "DD3") (pin "26") (pinfunction "PC3_26") (pintype "passive"))
      (node (ref "VD6") (pin "2") (pinfunction "A_2") (pintype "passive"))
    )
    (net (code "35") (name "Net-(DD3-PC6{slash}!RESET)") (class "Default")
      (node (ref "DD3") (pin "29") (pinfunction "PC6/!RESET_29") (pintype "passive"))
      (node (ref "R3") (pin "1") (pinfunction "1_1") (pintype "passive"))
      (node (ref "R4") (pin "1") (pinfunction "1_1") (pintype "passive"))
      (node (ref "SB1") (pin "3") (pinfunction "3_3") (pintype "passive"))
      (node (ref "XS3") (pin "2") (pinfunction "PGC_2") (pintype "passive"))
    )
    (net (code "36") (name "Net-(DD3-PD2)") (class "Default")
      (node (ref "DD3") (pin "32") (pinfunction "PD2_32") (pintype "passive"))
      (node (ref "SB11") (pin "1") (pinfunction "1_1") (pintype "passive"))
      (node (ref "SB3") (pin "1") (pinfunction "1_1") (pintype "passive"))
      (node (ref "SB7") (pin "1") (pinfunction "1_1") (pintype "passive"))
    )
    (net (code "37") (name "Net-(DD3-PD3)") (class "Default")
      (node (ref "DD3") (pin "1") (pinfunction "PD3_1") (pintype "passive"))
      (node (ref "SB10") (pin "1") (pinfunction "1_1") (pintype "passive"))
      (node (ref "SB2") (pin "1") (pinfunction "1_1") (pintype "passive"))
      (node (ref "SB6") (pin "1") (pinfunction "1_1") (pintype "passive"))
    )
    (net (code "38") (name "Net-(DD3-PD4)") (class "Default")
      (node (ref "BA1") (pin "P") (pinfunction "P_P") (pintype "passive"))
      (node (ref "DD3") (pin "2") (pinfunction "PD4_2") (pintype "passive"))
    )
    (net (code "39") (name "Net-(DD3-PD5)") (class "Default")
      (node (ref "DD3") (pin "9") (pinfunction "PD5_9") (pintype "passive"))
      (node (ref "XS8") (pin "02") (pinfunction "02_02") (pintype "passive"))
    )
    (net (code "40") (name "Net-(DD3-PD6)") (class "Default")
      (node (ref "DD3") (pin "10") (pinfunction "PD6_10") (pintype "passive"))
      (node (ref "PS1") (pin "3") (pinfunction "ECHO_3") (pintype "passive"))
    )
    (net (code "41") (name "Net-(DD3-PD7)") (class "Default")
      (node (ref "DD3") (pin "11") (pinfunction "PD7_11") (pintype "passive"))
      (node (ref "PS1") (pin "2") (pinfunction "TRIG_2") (pintype "passive"))
    )
    (net (code "42") (name "Net-(VD1-PadA)") (class "Default")
      (node (ref "VD1") (pin "A") (pinfunction "A_A") (pintype "passive"))
      (node (ref "XS1") (pin "2") (pinfunction "2_2") (pintype "passive"))
    )
    (net (code "43") (name "Net-(VD2-A)") (class "Default")
      (node (ref "R5") (pin "2") (pinfunction "2_2") (pintype "passive"))
      (node (ref "VD2") (pin "2") (pinfunction "A_2") (pintype "passive"))
    )
    (net (code "44") (name "Net-(VD3-A)") (class "Default")
      (node (ref "R6") (pin "1") (pinfunction "1_1") (pintype "passive"))
      (node (ref "VD3") (pin "2") (pinfunction "A_2") (pintype "passive"))
    )
    (net (code "45") (name "Net-(VD4-A)") (class "Default")
      (node (ref "R9") (pin "1") (pinfunction "1_1") (pintype "passive"))
      (node (ref "VD4") (pin "2") (pinfunction "A_2") (pintype "passive"))
    )
    (net (code "46") (name "Net-(VD5-A)") (class "Default")
      (node (ref "R11") (pin "1") (pinfunction "1_1") (pintype "passive"))
      (node (ref "VD5") (pin "2") (pinfunction "A_2") (pintype "passive"))
    )
    (net (code "47") (name "Net-(VD6-C)") (class "Default")
      (node (ref "R12") (pin "1") (pinfunction "1_1") (pintype "passive"))
      (node (ref "VD6") (pin "4") (pinfunction "C_4") (pintype "passive"))
      (node (ref "VD7") (pin "4") (pinfunction "C_4") (pintype "passive"))
    )
    (net (code "48") (name "Net-(VT1-D)") (class "Default")
      (node (ref "VT1") (pin "3") (pinfunction "D_3") (pintype "passive"))
      (node (ref "XS2") (pin "1") (pinfunction "VCC_1") (pintype "passive"))
    )
    (net (code "49") (name "VCC") (class "Default")
      (node (ref "C1") (pin "P") (pinfunction "P_P") (pintype "passive"))
      (node (ref "C2") (pin "P") (pinfunction "P_P") (pintype "passive"))
      (node (ref "C3") (pin "2") (pinfunction "2_2") (pintype "passive"))
      (node (ref "C4") (pin "2") (pinfunction "2_2") (pintype "passive"))
      (node (ref "C7") (pin "1") (pinfunction "1_1") (pintype "passive"))
      (node (ref "C9") (pin "2") (pinfunction "2_2") (pintype "passive"))
      (node (ref "DA1") (pin "2") (pinfunction "OUT_2") (pintype "passive"))
      (node (ref "DA1") (pin "3") (pinfunction "IN_3") (pintype "passive"))
      (node (ref "DA1") (pin "4") (pinfunction "OUT_4") (pintype "passive"))
      (node (ref "DA2") (pin "2") (pinfunction "IN1-_2") (pintype "passive"))
      (node (ref "DA2") (pin "8") (pinfunction "V+_8") (pintype "passive"))
      (node (ref "DD1") (pin "16") (pinfunction "VCC_16") (pintype "passive"))
      (node (ref "DD3") (pin "18") (pinfunction "AVCC_18") (pintype "passive"))
      (node (ref "DD3") (pin "4") (pinfunction "VCC_4") (pintype "passive"))
      (node (ref "DD3") (pin "6") (pinfunction "VCC_6") (pintype "passive"))
      (node (ref "PS1") (pin "1") (pinfunction "VCC_1") (pintype "passive"))
      (node (ref "R1") (pin "2") (pinfunction "2_2") (pintype "passive"))
      (node (ref "R11") (pin "2") (pinfunction "2_2") (pintype "passive"))
      (node (ref "R3") (pin "2") (pinfunction "2_2") (pintype "passive"))
      (node (ref "R4") (pin "2") (pinfunction "2_2") (pintype "passive"))
      (node (ref "R6") (pin "2") (pinfunction "2_2") (pintype "passive"))
      (node (ref "R9") (pin "2") (pinfunction "2_2") (pintype "passive"))
      (node (ref "VD1") (pin "C") (pinfunction "C_C") (pintype "passive"))
      (node (ref "VT1") (pin "2") (pinfunction "S_2") (pintype "passive"))
      (node (ref "XS3") (pin "5") (pinfunction "VCC_5") (pintype "passive"))
      (node (ref "XS4") (pin "01") (pinfunction "01_01") (pintype "passive"))
      (node (ref "XS6") (pin "03") (pinfunction "03_03") (pintype "passive"))
      (node (ref "XS7") (pin "03") (pinfunction "03_03") (pintype "passive"))
      (node (ref "XS8") (pin "01") (pinfunction "01_01") (pintype "passive"))
    )
    (net (code "50") (name "unconnected-(DD1-DTR-Pad13)") (class "Default")
      (node (ref "DD1") (pin "13") (pinfunction "DTR_13") (pintype "passive"))
    )
    (net (code "51") (name "unconnected-(DD1-R232-Pad15)") (class "Default")
      (node (ref "DD1") (pin "15") (pinfunction "R232_15") (pintype "passive"))
    )
    (net (code "52") (name "unconnected-(DD1-RTS-Pad14)") (class "Default")
      (node (ref "DD1") (pin "14") (pinfunction "RTS_14") (pintype "passive"))
    )
    (net (code "53") (name "unconnected-(DD2-GND-Pad8)") (class "Default")
      (node (ref "DD2") (pin "8") (pinfunction "GND_8") (pintype "passive"))
    )
    (net (code "54") (name "unconnected-(DD2-P3-Pad7)") (class "Default")
      (node (ref "DD2") (pin "7") (pinfunction "P3_7") (pintype "passive"))
    )
    (net (code "55") (name "unconnected-(DD2-VCC-Pad16)") (class "Default")
      (node (ref "DD2") (pin "16") (pinfunction "VCC_16") (pintype "passive"))
    )
    (net (code "56") (name "unconnected-(DD2-~{INT}-Pad13)") (class "Default")
      (node (ref "DD2") (pin "13") (pinfunction "~{INT}_13") (pintype "passive"))
    )
    (net (code "57") (name "unconnected-(DD3-ADC6-Pad19)") (class "Default")
      (node (ref "DD3") (pin "19") (pinfunction "ADC6_19") (pintype "passive"))
    )
    (net (code "58") (name "unconnected-(DD3-ADC7-Pad22)") (class "Default")
      (node (ref "DD3") (pin "22") (pinfunction "ADC7_22") (pintype "passive"))
    )
    (net (code "59") (name "unconnected-(DD3-PB2-Pad14)") (class "Default")
      (node (ref "DD3") (pin "14") (pinfunction "PB2_14") (pintype "passive"))
    )
    (net (code "60") (name "unconnected-(DD3-PC0-Pad23)") (class "Default")
      (node (ref "DD3") (pin "23") (pinfunction "PC0_23") (pintype "passive"))
    )
    (net (code "61") (name "unconnected-(DD3-PC1-Pad24)") (class "Default")
      (node (ref "DD3") (pin "24") (pinfunction "PC1_24") (pintype "passive"))
    )
    (net (code "62") (name "unconnected-(HL1-A-Pad15)") (class "Default")
      (node (ref "HL1") (pin "15") (pinfunction "A_15") (pintype "passive"))
    )
    (net (code "63") (name "unconnected-(HL1-DB0-Pad7)") (class "Default")
      (node (ref "HL1") (pin "7") (pinfunction "DB0_7") (pintype "passive"))
    )
    (net (code "64") (name "unconnected-(HL1-DB1-Pad8)") (class "Default")
      (node (ref "HL1") (pin "8") (pinfunction "DB1_8") (pintype "passive"))
    )
    (net (code "65") (name "unconnected-(HL1-DB2-Pad9)") (class "Default")
      (node (ref "HL1") (pin "9") (pinfunction "DB2_9") (pintype "passive"))
    )
    (net (code "66") (name "unconnected-(HL1-DB3-Pad10)") (class "Default")
      (node (ref "HL1") (pin "10") (pinfunction "DB3_10") (pintype "passive"))
    )
    (net (code "67") (name "unconnected-(HL1-K-Pad16)") (class "Default")
      (node (ref "HL1") (pin "16") (pinfunction "K_16") (pintype "passive"))
    )
    (net (code "68") (name "unconnected-(HL1-SHIELD-PadS1)") (class "Default")
      (node (ref "HL1") (pin "S1") (pinfunction "SHIELD_S1") (pintype "passive"))
    )
    (net (code "69") (name "unconnected-(HL1-SHIELD-PadS2)") (class "Default")
      (node (ref "HL1") (pin "S2") (pinfunction "SHIELD_S2") (pintype "passive"))
    )
    (net (code "70") (name "unconnected-(HL1-SHIELD-PadS3)") (class "Default")
      (node (ref "HL1") (pin "S3") (pinfunction "SHIELD_S3") (pintype "passive"))
    )
    (net (code "71") (name "unconnected-(HL1-SHIELD-PadS4)") (class "Default")
      (node (ref "HL1") (pin "S4") (pinfunction "SHIELD_S4") (pintype "passive"))
    )
    (net (code "72") (name "unconnected-(HL1-V0-Pad3)") (class "Default")
      (node (ref "HL1") (pin "3") (pinfunction "V0_3") (pintype "passive"))
    )
    (net (code "73") (name "unconnected-(HL1-VDD-Pad2)") (class "Default")
      (node (ref "HL1") (pin "2") (pinfunction "VDD_2") (pintype "passive"))
    )
    (net (code "74") (name "unconnected-(SB1-Pad2)") (class "Default")
      (node (ref "SB1") (pin "2") (pinfunction "2_2") (pintype "passive"))
    )
    (net (code "75") (name "unconnected-(SB1-Pad4)") (class "Default")
      (node (ref "SB1") (pin "4") (pinfunction "4_4") (pintype "passive"))
    )
    (net (code "76") (name "unconnected-(SB2-Pad2)") (class "Default")
      (node (ref "SB2") (pin "2") (pinfunction "2_2") (pintype "passive"))
    )
    (net (code "77") (name "unconnected-(SB2-Pad4)") (class "Default")
      (node (ref "SB2") (pin "4") (pinfunction "4_4") (pintype "passive"))
    )
    (net (code "78") (name "unconnected-(SB3-Pad2)") (class "Default")
      (node (ref "SB3") (pin "2") (pinfunction "2_2") (pintype "passive"))
    )
    (net (code "79") (name "unconnected-(SB3-Pad4)") (class "Default")
      (node (ref "SB3") (pin "4") (pinfunction "4_4") (pintype "passive"))
    )
    (net (code "80") (name "unconnected-(SB4-Pad2)") (class "Default")
      (node (ref "SB4") (pin "2") (pinfunction "2_2") (pintype "passive"))
    )
    (net (code "81") (name "unconnected-(SB4-Pad4)") (class "Default")
      (node (ref "SB4") (pin "4") (pinfunction "4_4") (pintype "passive"))
    )
    (net (code "82") (name "unconnected-(SB5-Pad2)") (class "Default")
      (node (ref "SB5") (pin "2") (pinfunction "2_2") (pintype "passive"))
    )
    (net (code "83") (name "unconnected-(SB5-Pad4)") (class "Default")
      (node (ref "SB5") (pin "4") (pinfunction "4_4") (pintype "passive"))
    )
    (net (code "84") (name "unconnected-(SB6-Pad2)") (class "Default")
      (node (ref "SB6") (pin "2") (pinfunction "2_2") (pintype "passive"))
    )
    (net (code "85") (name "unconnected-(SB6-Pad4)") (class "Default")
      (node (ref "SB6") (pin "4") (pinfunction "4_4") (pintype "passive"))
    )
    (net (code "86") (name "unconnected-(SB7-Pad2)") (class "Default")
      (node (ref "SB7") (pin "2") (pinfunction "2_2") (pintype "passive"))
    )
    (net (code "87") (name "unconnected-(SB7-Pad4)") (class "Default")
      (node (ref "SB7") (pin "4") (pinfunction "4_4") (pintype "passive"))
    )
    (net (code "88") (name "unconnected-(SB8-Pad2)") (class "Default")
      (node (ref "SB8") (pin "2") (pinfunction "2_2") (pintype "passive"))
    )
    (net (code "89") (name "unconnected-(SB8-Pad4)") (class "Default")
      (node (ref "SB8") (pin "4") (pinfunction "4_4") (pintype "passive"))
    )
    (net (code "90") (name "unconnected-(SB9-Pad2)") (class "Default")
      (node (ref "SB9") (pin "2") (pinfunction "2_2") (pintype "passive"))
    )
    (net (code "91") (name "unconnected-(SB9-Pad4)") (class "Default")
      (node (ref "SB9") (pin "4") (pinfunction "4_4") (pintype "passive"))
    )
    (net (code "92") (name "unconnected-(SB10-Pad2)") (class "Default")
      (node (ref "SB10") (pin "2") (pinfunction "2_2") (pintype "passive"))
    )
    (net (code "93") (name "unconnected-(SB10-Pad4)") (class "Default")
      (node (ref "SB10") (pin "4") (pinfunction "4_4") (pintype "passive"))
    )
    (net (code "94") (name "unconnected-(SB11-Pad2)") (class "Default")
      (node (ref "SB11") (pin "2") (pinfunction "2_2") (pintype "passive"))
    )
    (net (code "95") (name "unconnected-(SB11-Pad4)") (class "Default")
      (node (ref "SB11") (pin "4") (pinfunction "4_4") (pintype "passive"))
    )
    (net (code "96") (name "unconnected-(SB12-Pad2)") (class "Default")
      (node (ref "SB12") (pin "2") (pinfunction "2_2") (pintype "passive"))
    )
    (net (code "97") (name "unconnected-(SB12-Pad4)") (class "Default")
      (node (ref "SB12") (pin "4") (pinfunction "4_4") (pintype "passive"))
    )
    (net (code "98") (name "unconnected-(SB13-Pad2)") (class "Default")
      (node (ref "SB13") (pin "2") (pinfunction "2_2") (pintype "passive"))
    )
    (net (code "99") (name "unconnected-(SB13-Pad4)") (class "Default")
      (node (ref "SB13") (pin "4") (pinfunction "4_4") (pintype "passive"))
    )
    (net (code "100") (name "unconnected-(XS2-SHIELD-PadS1)") (class "Default")
      (node (ref "XS2") (pin "S1") (pinfunction "SHIELD_S1") (pintype "passive"))
    )
    (net (code "101") (name "unconnected-(XS2-SHIELD-PadS2)") (class "Default")
      (node (ref "XS2") (pin "S2") (pinfunction "SHIELD_S2") (pintype "passive"))
    )
    (net (code "102") (name "unconnected-(ZQ2-Pad1)") (class "Default")
      (node (ref "ZQ2") (pin "1") (pinfunction "1_1") (pintype "passive"))
    )
  )
)
